# BPF.net
KiCad netlist of a schematic drawn in Altium Designer
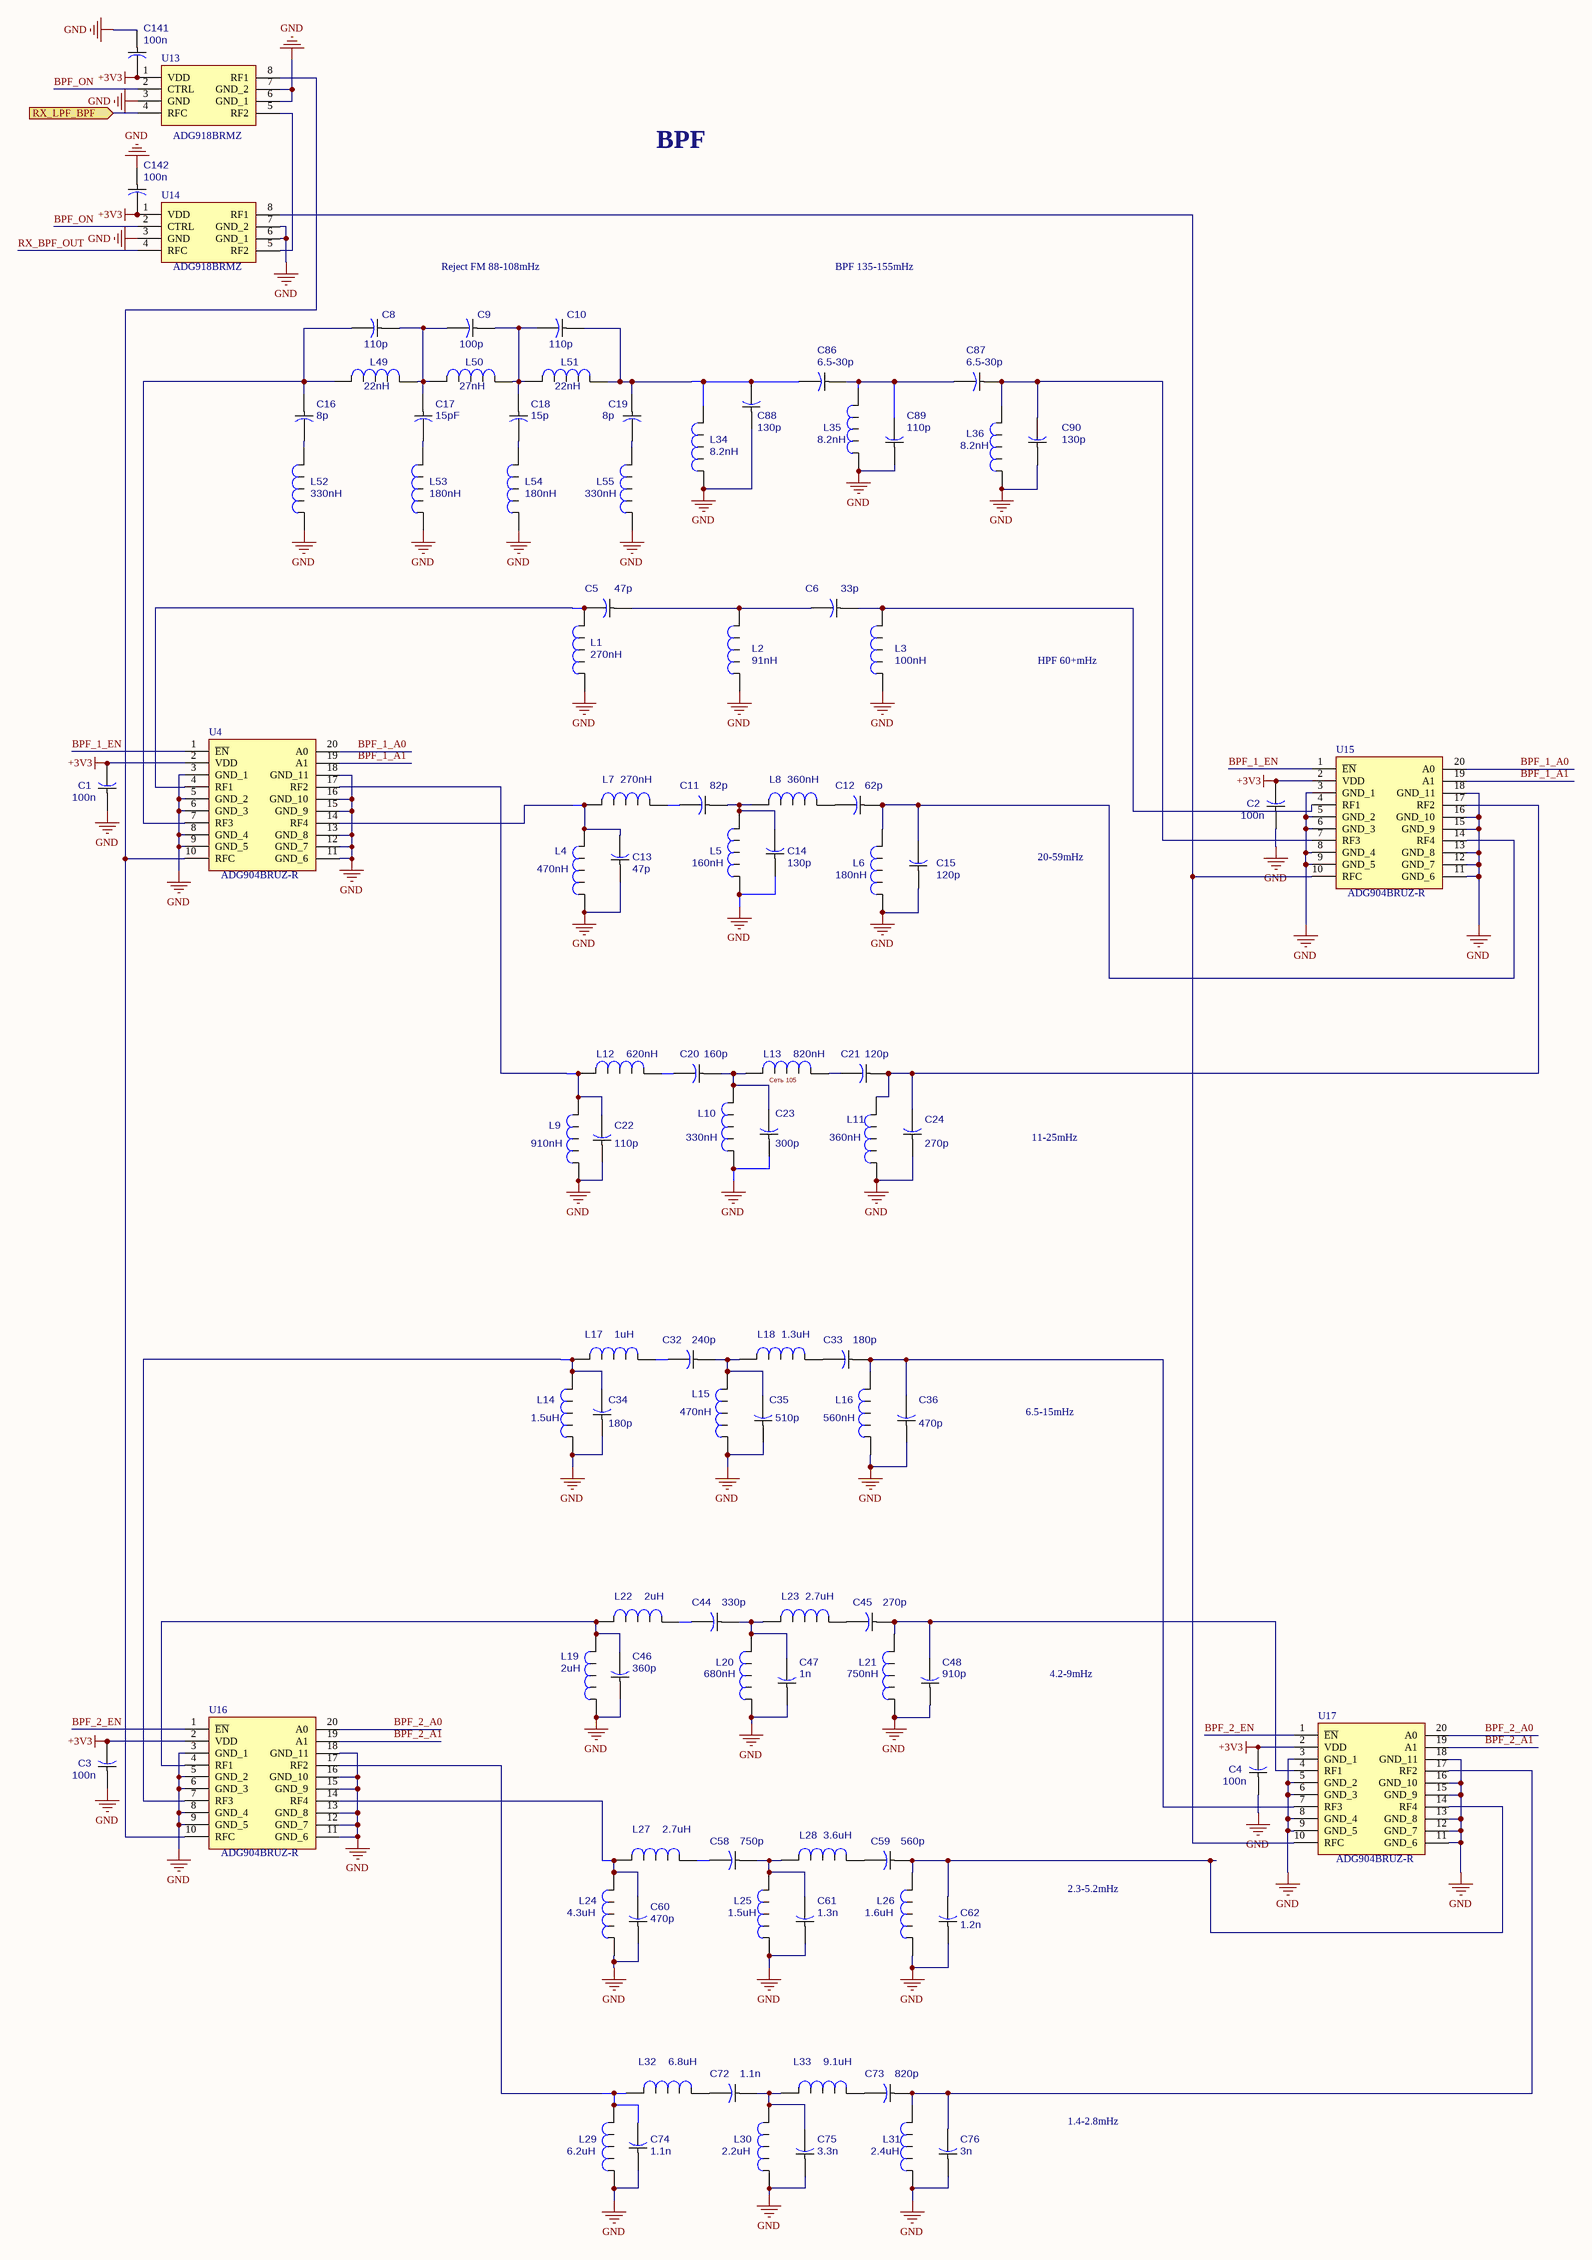
[diagram p0: BPF.SchDoc]

(export (version "E")
  (design (tool "Eeschema 10.0.6"))
  (components
    (comp (ref "C1")
      (value "100n")
      (footprint "CAP_0805")
      (description "CAP_0805")
      (libsource (lib "*") (part "CAP_0805"))
    )
    (comp (ref "C2")
      (value "100n")
      (footprint "CAP_0805")
      (description "CAP_0805")
      (libsource (lib "*") (part "CAP_0805"))
    )
    (comp (ref "C3")
      (value "100n")
      (footprint "CAP_0805")
      (description "CAP_0805")
      (libsource (lib "*") (part "CAP_0805"))
    )
    (comp (ref "C4")
      (value "100n")
      (footprint "CAP_0805")
      (description "CAP_0805")
      (libsource (lib "*") (part "CAP_0805"))
    )
    (comp (ref "C5")
      (value "47p")
      (footprint "CAP_0805")
      (description "CAP_0805")
      (libsource (lib "*") (part "CAP_0805"))
    )
    (comp (ref "C6")
      (value "33p")
      (footprint "CAP_0805")
      (description "CAP_0805")
      (libsource (lib "*") (part "CAP_0805"))
    )
    (comp (ref "C8")
      (value "110p")
      (footprint "CAP_0805")
      (description "CAP_0805")
      (libsource (lib "*") (part "CAP_0805"))
    )
    (comp (ref "C9")
      (value "100p")
      (footprint "CAP_0805")
      (description "CAP_0805")
      (libsource (lib "*") (part "CAP_0805"))
    )
    (comp (ref "C10")
      (value "110p")
      (footprint "CAP_0805")
      (description "CAP_0805")
      (libsource (lib "*") (part "CAP_0805"))
    )
    (comp (ref "C11")
      (value "82p")
      (footprint "CAP_0805")
      (description "CAP_0805")
      (libsource (lib "*") (part "CAP_0805"))
    )
    (comp (ref "C12")
      (value "62p")
      (footprint "CAP_0805")
      (description "CAP_0805")
      (libsource (lib "*") (part "CAP_0805"))
    )
    (comp (ref "C13")
      (value "47p")
      (footprint "CAP_0805")
      (description "CAP_0805")
      (libsource (lib "*") (part "CAP_0805"))
    )
    (comp (ref "C14")
      (value "130p")
      (footprint "CAP_0805")
      (description "CAP_0805")
      (libsource (lib "*") (part "CAP_0805"))
    )
    (comp (ref "C15")
      (value "120p")
      (footprint "CAP_0805")
      (description "CAP_0805")
      (libsource (lib "*") (part "CAP_0805"))
    )
    (comp (ref "C16")
      (value "8p")
      (footprint "CAP_0805")
      (description "CAP_0805")
      (libsource (lib "*") (part "CAP_0805"))
    )
    (comp (ref "C17")
      (value "15pF")
      (footprint "CAP_0805")
      (description "CAP_0805")
      (libsource (lib "*") (part "CAP_0805"))
    )
    (comp (ref "C18")
      (value "15p")
      (footprint "CAP_0805")
      (description "CAP_0805")
      (libsource (lib "*") (part "CAP_0805"))
    )
    (comp (ref "C19")
      (value "8p")
      (footprint "CAP_0805")
      (description "CAP_0805")
      (libsource (lib "*") (part "CAP_0805"))
    )
    (comp (ref "C20")
      (value "160p")
      (footprint "CAP_0805")
      (description "CAP_0805")
      (libsource (lib "*") (part "CAP_0805"))
    )
    (comp (ref "C21")
      (value "120p")
      (footprint "CAP_0805")
      (description "CAP_0805")
      (libsource (lib "*") (part "CAP_0805"))
    )
    (comp (ref "C22")
      (value "110p")
      (footprint "CAP_0805")
      (description "CAP_0805")
      (libsource (lib "*") (part "CAP_0805"))
    )
    (comp (ref "C23")
      (value "300p")
      (footprint "CAP_0805")
      (description "CAP_0805")
      (libsource (lib "*") (part "CAP_0805"))
    )
    (comp (ref "C24")
      (value "270p")
      (footprint "CAP_0805")
      (description "CAP_0805")
      (libsource (lib "*") (part "CAP_0805"))
    )
    (comp (ref "C32")
      (value "240p")
      (footprint "CAP_0805")
      (description "CAP_0805")
      (libsource (lib "*") (part "CAP_0805"))
    )
    (comp (ref "C33")
      (value "180p")
      (footprint "CAP_0805")
      (description "CAP_0805")
      (libsource (lib "*") (part "CAP_0805"))
    )
    (comp (ref "C34")
      (value "180p")
      (footprint "CAP_0805")
      (description "CAP_0805")
      (libsource (lib "*") (part "CAP_0805"))
    )
    (comp (ref "C35")
      (value "510p")
      (footprint "CAP_0805")
      (description "CAP_0805")
      (libsource (lib "*") (part "CAP_0805"))
    )
    (comp (ref "C36")
      (value "470p")
      (footprint "CAP_0805")
      (description "CAP_0805")
      (libsource (lib "*") (part "CAP_0805"))
    )
    (comp (ref "C44")
      (value "330p")
      (footprint "CAP_0805")
      (description "CAP_0805")
      (libsource (lib "*") (part "CAP_0805"))
    )
    (comp (ref "C45")
      (value "270p")
      (footprint "CAP_0805")
      (description "CAP_0805")
      (libsource (lib "*") (part "CAP_0805"))
    )
    (comp (ref "C46")
      (value "360p")
      (footprint "CAP_0805")
      (description "CAP_0805")
      (libsource (lib "*") (part "CAP_0805"))
    )
    (comp (ref "C47")
      (value "1n")
      (footprint "CAP_0805")
      (description "CAP_0805")
      (libsource (lib "*") (part "CAP_0805"))
    )
    (comp (ref "C48")
      (value "910p")
      (footprint "CAP_0805")
      (description "CAP_0805")
      (libsource (lib "*") (part "CAP_0805"))
    )
    (comp (ref "C58")
      (value "750p")
      (footprint "CAP_0805")
      (description "CAP_0805")
      (libsource (lib "*") (part "CAP_0805"))
    )
    (comp (ref "C59")
      (value "560p")
      (footprint "CAP_0805")
      (description "CAP_0805")
      (libsource (lib "*") (part "CAP_0805"))
    )
    (comp (ref "C60")
      (value "470p")
      (footprint "CAP_0805")
      (description "CAP_0805")
      (libsource (lib "*") (part "CAP_0805"))
    )
    (comp (ref "C61")
      (value "1.3n")
      (footprint "CAP_0805")
      (description "CAP_0805")
      (libsource (lib "*") (part "CAP_0805"))
    )
    (comp (ref "C62")
      (value "1.2n")
      (footprint "CAP_0805")
      (description "CAP_0805")
      (libsource (lib "*") (part "CAP_0805"))
    )
    (comp (ref "C72")
      (value "1.1n")
      (footprint "CAP_0805")
      (description "CAP_0805")
      (libsource (lib "*") (part "CAP_0805"))
    )
    (comp (ref "C73")
      (value "820p")
      (footprint "CAP_0805")
      (description "CAP_0805")
      (libsource (lib "*") (part "CAP_0805"))
    )
    (comp (ref "C74")
      (value "1.1n")
      (footprint "CAP_0805")
      (description "CAP_0805")
      (libsource (lib "*") (part "CAP_0805"))
    )
    (comp (ref "C75")
      (value "3.3n")
      (footprint "CAP_0805")
      (description "CAP_0805")
      (libsource (lib "*") (part "CAP_0805"))
    )
    (comp (ref "C76")
      (value "3n")
      (footprint "CAP_0805")
      (description "CAP_0805")
      (libsource (lib "*") (part "CAP_0805"))
    )
    (comp (ref "C86")
      (value "6.5-30p")
      (footprint "5025[2010]")
      (description "TZC3P300A110")
      (libsource (lib "*") (part "CAP_0805"))
    )
    (comp (ref "C87")
      (value "6.5-30p")
      (footprint "5025[2010]")
      (description "TZC3P300A110")
      (libsource (lib "*") (part "CAP_0805"))
    )
    (comp (ref "C88")
      (value "130p")
      (footprint "CAP_0805")
      (description "CAP_0805")
      (libsource (lib "*") (part "CAP_0805"))
    )
    (comp (ref "C89")
      (value "110p")
      (footprint "CAP_0805")
      (description "CAP_0805")
      (libsource (lib "*") (part "CAP_0805"))
    )
    (comp (ref "C90")
      (value "130p")
      (footprint "CAP_0805")
      (description "CAP_0805")
      (libsource (lib "*") (part "CAP_0805"))
    )
    (comp (ref "C141")
      (value "100n")
      (footprint "CAP_0805")
      (description "CAP_0805")
      (libsource (lib "*") (part "CAP_0805"))
    )
    (comp (ref "C142")
      (value "100n")
      (footprint "CAP_0805")
      (description "CAP_0805")
      (libsource (lib "*") (part "CAP_0805"))
    )
    (comp (ref "L1")
      (value "270nH")
      (footprint "IND_0805")
      (description "IND_0805")
      (libsource (lib "*") (part "IND_0805"))
    )
    (comp (ref "L2")
      (value "91nH")
      (footprint "IND_0805")
      (description "IND_0805")
      (libsource (lib "*") (part "IND_0805"))
    )
    (comp (ref "L3")
      (value "100nH")
      (footprint "IND_0805")
      (description "IND_0805")
      (libsource (lib "*") (part "IND_0805"))
    )
    (comp (ref "L4")
      (value "470nH")
      (footprint "IND_0805")
      (description "IND_0805")
      (libsource (lib "*") (part "IND_0805"))
    )
    (comp (ref "L5")
      (value "160nH")
      (footprint "IND_0805")
      (description "IND_0805")
      (libsource (lib "*") (part "IND_0805"))
    )
    (comp (ref "L6")
      (value "180nH")
      (footprint "IND_0805")
      (description "IND_0805")
      (libsource (lib "*") (part "IND_0805"))
    )
    (comp (ref "L7")
      (value "270nH")
      (footprint "IND_0805")
      (description "IND_0805")
      (libsource (lib "*") (part "IND_0805"))
    )
    (comp (ref "L8")
      (value "360nH")
      (footprint "IND_0805")
      (description "IND_0805")
      (libsource (lib "*") (part "IND_0805"))
    )
    (comp (ref "L9")
      (value "910nH")
      (footprint "IND_0805")
      (description "IND_0805")
      (libsource (lib "*") (part "IND_0805"))
    )
    (comp (ref "L10")
      (value "330nH")
      (footprint "IND_0805")
      (description "IND_0805")
      (libsource (lib "*") (part "IND_0805"))
    )
    (comp (ref "L11")
      (value "360nH")
      (footprint "IND_0805")
      (description "IND_0805")
      (libsource (lib "*") (part "IND_0805"))
    )
    (comp (ref "L12")
      (value "620nH")
      (footprint "IND_0805")
      (description "IND_0805")
      (libsource (lib "*") (part "IND_0805"))
    )
    (comp (ref "L13")
      (value "820nH")
      (footprint "IND_0805")
      (description "IND_0805")
      (libsource (lib "*") (part "IND_0805"))
    )
    (comp (ref "L14")
      (value "1.5uH")
      (footprint "IND_0805")
      (description "IND_0805")
      (libsource (lib "*") (part "IND_0805"))
    )
    (comp (ref "L15")
      (value "470nH")
      (footprint "IND_0805")
      (description "IND_0805")
      (libsource (lib "*") (part "IND_0805"))
    )
    (comp (ref "L16")
      (value "560nH")
      (footprint "IND_0805")
      (description "IND_0805")
      (libsource (lib "*") (part "IND_0805"))
    )
    (comp (ref "L17")
      (value "1uH")
      (footprint "IND_0805")
      (description "IND_0805")
      (libsource (lib "*") (part "IND_0805"))
    )
    (comp (ref "L18")
      (value "1.3uH")
      (footprint "IND_0805")
      (description "IND_0805")
      (libsource (lib "*") (part "IND_0805"))
    )
    (comp (ref "L19")
      (value "2uH")
      (footprint "IND_0805")
      (description "IND_0805")
      (libsource (lib "*") (part "IND_0805"))
    )
    (comp (ref "L20")
      (value "680nH")
      (footprint "IND_0805")
      (description "IND_0805")
      (libsource (lib "*") (part "IND_0805"))
    )
    (comp (ref "L21")
      (value "750nH")
      (footprint "IND_0805")
      (description "IND_0805")
      (libsource (lib "*") (part "IND_0805"))
    )
    (comp (ref "L22")
      (value "2uH")
      (footprint "IND_0805")
      (description "IND_0805")
      (libsource (lib "*") (part "IND_0805"))
    )
    (comp (ref "L23")
      (value "2.7uH")
      (footprint "IND_0805")
      (description "IND_0805")
      (libsource (lib "*") (part "IND_0805"))
    )
    (comp (ref "L24")
      (value "4.3uH")
      (footprint "IND_0805")
      (description "IND_0805")
      (libsource (lib "*") (part "IND_0805"))
    )
    (comp (ref "L25")
      (value "1.5uH")
      (footprint "IND_0805")
      (description "IND_0805")
      (libsource (lib "*") (part "IND_0805"))
    )
    (comp (ref "L26")
      (value "1.6uH")
      (footprint "IND_0805")
      (description "IND_0805")
      (libsource (lib "*") (part "IND_0805"))
    )
    (comp (ref "L27")
      (value "2.7uH")
      (footprint "IND_0805")
      (description "IND_0805")
      (libsource (lib "*") (part "IND_0805"))
    )
    (comp (ref "L28")
      (value "3.6uH")
      (footprint "IND_0805")
      (description "IND_0805")
      (libsource (lib "*") (part "IND_0805"))
    )
    (comp (ref "L29")
      (value "6.2uH")
      (footprint "IND_0805")
      (description "IND_0805")
      (libsource (lib "*") (part "IND_0805"))
    )
    (comp (ref "L30")
      (value "2.2uH")
      (footprint "IND_0805")
      (description "IND_0805")
      (libsource (lib "*") (part "IND_0805"))
    )
    (comp (ref "L31")
      (value "2.4uH")
      (footprint "IND_0805")
      (description "IND_0805")
      (libsource (lib "*") (part "IND_0805"))
    )
    (comp (ref "L32")
      (value "6.8uH")
      (footprint "IND_0805")
      (description "IND_0805")
      (libsource (lib "*") (part "IND_0805"))
    )
    (comp (ref "L33")
      (value "9.1uH")
      (footprint "IND_0805")
      (description "IND_0805")
      (libsource (lib "*") (part "IND_0805"))
    )
    (comp (ref "L34")
      (value "8.2nH")
      (footprint "IND_0805")
      (description "IND_0805")
      (libsource (lib "*") (part "IND_0805"))
    )
    (comp (ref "L35")
      (value "8.2nH")
      (footprint "IND_0805")
      (description "IND_0805")
      (libsource (lib "*") (part "IND_0805"))
    )
    (comp (ref "L36")
      (value "8.2nH")
      (footprint "IND_0805")
      (description "IND_0805")
      (libsource (lib "*") (part "IND_0805"))
    )
    (comp (ref "L49")
      (value "22nH")
      (footprint "IND_0805")
      (description "IND_0805")
      (libsource (lib "*") (part "IND_0805"))
    )
    (comp (ref "L50")
      (value "27nH")
      (footprint "IND_0805")
      (description "IND_0805")
      (libsource (lib "*") (part "IND_0805"))
    )
    (comp (ref "L51")
      (value "22nH")
      (footprint "IND_0805")
      (description "IND_0805")
      (libsource (lib "*") (part "IND_0805"))
    )
    (comp (ref "L52")
      (value "330nH")
      (footprint "IND_0805")
      (description "IND_0805")
      (libsource (lib "*") (part "IND_0805"))
    )
    (comp (ref "L53")
      (value "180nH")
      (footprint "IND_0805")
      (description "IND_0805")
      (libsource (lib "*") (part "IND_0805"))
    )
    (comp (ref "L54")
      (value "180nH")
      (footprint "IND_0805")
      (description "IND_0805")
      (libsource (lib "*") (part "IND_0805"))
    )
    (comp (ref "L55")
      (value "330nH")
      (footprint "IND_0805")
      (description "IND_0805")
      (libsource (lib "*") (part "IND_0805"))
    )
    (comp (ref "U4")
      (value "ADG904BRUZ-R")
      (footprint "SamacSys:SOP65P640X120-20N")
      (description "Integrated Circuit")
      (fields
        (field (name "MOUSER PART NUMBER") "584-ADG904BRUZ-R")
        (field (name "RS PART NUMBER") "5385019P")
      )
      (libsource (lib "*") (part "ADG904BRUZ-R"))
    )
    (comp (ref "U13")
      (value "ADG918BRMZ")
      (footprint "SamacSys:SOP65P490X110-8N")
      (description "Integrated Circuit")
      (fields (field (name "MOUSER PART NUMBER") "584-ADG918BRMZ") (field (name "RS PART NUMBER") "4969212P"))
      (libsource (lib "*") (part "ADG918BRMZ"))
    )
    (comp (ref "U14")
      (value "ADG918BRMZ")
      (footprint "SamacSys:SOP65P490X110-8N")
      (description "Integrated Circuit")
      (fields (field (name "MOUSER PART NUMBER") "584-ADG918BRMZ") (field (name "RS PART NUMBER") "4969212P"))
      (libsource (lib "*") (part "ADG918BRMZ"))
    )
    (comp (ref "U15")
      (value "ADG904BRUZ-R")
      (footprint "SamacSys:SOP65P640X120-20N")
      (description "Integrated Circuit")
      (fields
        (field (name "MOUSER PART NUMBER") "584-ADG904BRUZ-R")
        (field (name "RS PART NUMBER") "5385019P")
      )
      (libsource (lib "*") (part "ADG904BRUZ-R"))
    )
    (comp (ref "U16")
      (value "ADG904BRUZ-R")
      (footprint "SamacSys:SOP65P640X120-20N")
      (description "Integrated Circuit")
      (fields
        (field (name "MOUSER PART NUMBER") "584-ADG904BRUZ-R")
        (field (name "RS PART NUMBER") "5385019P")
      )
      (libsource (lib "*") (part "ADG904BRUZ-R"))
    )
    (comp (ref "U17")
      (value "ADG904BRUZ-R")
      (footprint "SamacSys:SOP65P640X120-20N")
      (description "Integrated Circuit")
      (fields
        (field (name "MOUSER PART NUMBER") "584-ADG904BRUZ-R")
        (field (name "RS PART NUMBER") "5385019P")
      )
      (libsource (lib "*") (part "ADG904BRUZ-R"))
    )
  )
  (nets
    (net (code "1") (name "+3V3") (class "Default")
      (node (ref "C1") (pin "2") (pinfunction "2_2") (pintype "passive"))
      (node (ref "C141") (pin "2") (pinfunction "2_2") (pintype "passive"))
      (node (ref "C142") (pin "2") (pinfunction "2_2") (pintype "passive"))
      (node (ref "C2") (pin "2") (pinfunction "2_2") (pintype "passive"))
      (node (ref "C3") (pin "2") (pinfunction "2_2") (pintype "passive"))
      (node (ref "C4") (pin "2") (pinfunction "2_2") (pintype "passive"))
      (node (ref "U13") (pin "1") (pinfunction "VDD_1") (pintype "power_in"))
      (node (ref "U14") (pin "1") (pinfunction "VDD_1") (pintype "power_in"))
      (node (ref "U15") (pin "2") (pinfunction "VDD_2") (pintype "passive"))
      (node (ref "U16") (pin "2") (pinfunction "VDD_2") (pintype "passive"))
      (node (ref "U17") (pin "2") (pinfunction "VDD_2") (pintype "passive"))
      (node (ref "U4") (pin "2") (pinfunction "VDD_2") (pintype "passive"))
    )
    (net (code "2") (name "/BPF_1_A0") (class "Default")
      (node (ref "U15") (pin "20") (pinfunction "A0_20") (pintype "passive"))
      (node (ref "U4") (pin "20") (pinfunction "A0_20") (pintype "passive"))
    )
    (net (code "3") (name "/BPF_1_A1") (class "Default")
      (node (ref "U15") (pin "19") (pinfunction "A1_19") (pintype "passive"))
      (node (ref "U4") (pin "19") (pinfunction "A1_19") (pintype "passive"))
    )
    (net (code "4") (name "/BPF_1_EN") (class "Default")
      (node (ref "U15") (pin "1") (pinfunction "~{EN}_1") (pintype "passive"))
      (node (ref "U4") (pin "1") (pinfunction "~{EN}_1") (pintype "passive"))
    )
    (net (code "5") (name "/BPF_2_A0") (class "Default")
      (node (ref "U16") (pin "20") (pinfunction "A0_20") (pintype "passive"))
      (node (ref "U17") (pin "20") (pinfunction "A0_20") (pintype "passive"))
    )
    (net (code "6") (name "/BPF_2_A1") (class "Default")
      (node (ref "U16") (pin "19") (pinfunction "A1_19") (pintype "passive"))
      (node (ref "U17") (pin "19") (pinfunction "A1_19") (pintype "passive"))
    )
    (net (code "7") (name "/BPF_2_EN") (class "Default")
      (node (ref "U16") (pin "1") (pinfunction "~{EN}_1") (pintype "passive"))
      (node (ref "U17") (pin "1") (pinfunction "~{EN}_1") (pintype "passive"))
    )
    (net (code "8") (name "/BPF_ON") (class "Default")
      (node (ref "U13") (pin "2") (pinfunction "CTRL_2") (pintype "passive"))
      (node (ref "U14") (pin "2") (pinfunction "CTRL_2") (pintype "passive"))
    )
    (net (code "9") (name "/RX_BPF_OUT") (class "Default")
      (node (ref "U14") (pin "4") (pinfunction "RFC_4") (pintype "passive"))
    )
    (net (code "10") (name "/RX_LPF_BPF") (class "Default")
      (node (ref "U13") (pin "4") (pinfunction "RFC_4") (pintype "passive"))
    )
    (net (code "11") (name "/Сеть 105") (class "Default")
      (node (ref "C20") (pin "1") (pinfunction "1_1") (pintype "passive"))
      (node (ref "C23") (pin "2") (pinfunction "2_2") (pintype "passive"))
      (node (ref "L10") (pin "2") (pinfunction "2_2") (pintype "passive"))
      (node (ref "L13") (pin "1") (pinfunction "1_1") (pintype "passive"))
    )
    (net (code "12") (name "GND") (class "Default")
      (node (ref "C1") (pin "1") (pinfunction "1_1") (pintype "passive"))
      (node (ref "C13") (pin "1") (pinfunction "1_1") (pintype "passive"))
      (node (ref "C14") (pin "1") (pinfunction "1_1") (pintype "passive"))
      (node (ref "C141") (pin "1") (pinfunction "1_1") (pintype "passive"))
      (node (ref "C142") (pin "1") (pinfunction "1_1") (pintype "passive"))
      (node (ref "C15") (pin "1") (pinfunction "1_1") (pintype "passive"))
      (node (ref "C2") (pin "1") (pinfunction "1_1") (pintype "passive"))
      (node (ref "C22") (pin "1") (pinfunction "1_1") (pintype "passive"))
      (node (ref "C23") (pin "1") (pinfunction "1_1") (pintype "passive"))
      (node (ref "C24") (pin "1") (pinfunction "1_1") (pintype "passive"))
      (node (ref "C3") (pin "1") (pinfunction "1_1") (pintype "passive"))
      (node (ref "C34") (pin "1") (pinfunction "1_1") (pintype "passive"))
      (node (ref "C35") (pin "1") (pinfunction "1_1") (pintype "passive"))
      (node (ref "C36") (pin "1") (pinfunction "1_1") (pintype "passive"))
      (node (ref "C4") (pin "1") (pinfunction "1_1") (pintype "passive"))
      (node (ref "C46") (pin "1") (pinfunction "1_1") (pintype "passive"))
      (node (ref "C47") (pin "1") (pinfunction "1_1") (pintype "passive"))
      (node (ref "C48") (pin "1") (pinfunction "1_1") (pintype "passive"))
      (node (ref "C60") (pin "1") (pinfunction "1_1") (pintype "passive"))
      (node (ref "C61") (pin "1") (pinfunction "1_1") (pintype "passive"))
      (node (ref "C62") (pin "1") (pinfunction "1_1") (pintype "passive"))
      (node (ref "C74") (pin "1") (pinfunction "1_1") (pintype "passive"))
      (node (ref "C75") (pin "1") (pinfunction "1_1") (pintype "passive"))
      (node (ref "C76") (pin "1") (pinfunction "1_1") (pintype "passive"))
      (node (ref "C88") (pin "1") (pinfunction "1_1") (pintype "passive"))
      (node (ref "C89") (pin "1") (pinfunction "1_1") (pintype "passive"))
      (node (ref "C90") (pin "1") (pinfunction "1_1") (pintype "passive"))
      (node (ref "L1") (pin "1") (pinfunction "1_1") (pintype "passive"))
      (node (ref "L10") (pin "1") (pinfunction "1_1") (pintype "passive"))
      (node (ref "L11") (pin "1") (pinfunction "1_1") (pintype "passive"))
      (node (ref "L14") (pin "1") (pinfunction "1_1") (pintype "passive"))
      (node (ref "L15") (pin "1") (pinfunction "1_1") (pintype "passive"))
      (node (ref "L16") (pin "1") (pinfunction "1_1") (pintype "passive"))
      (node (ref "L19") (pin "1") (pinfunction "1_1") (pintype "passive"))
      (node (ref "L2") (pin "1") (pinfunction "1_1") (pintype "passive"))
      (node (ref "L20") (pin "1") (pinfunction "1_1") (pintype "passive"))
      (node (ref "L21") (pin "1") (pinfunction "1_1") (pintype "passive"))
      (node (ref "L24") (pin "1") (pinfunction "1_1") (pintype "passive"))
      (node (ref "L25") (pin "1") (pinfunction "1_1") (pintype "passive"))
      (node (ref "L26") (pin "1") (pinfunction "1_1") (pintype "passive"))
      (node (ref "L29") (pin "1") (pinfunction "1_1") (pintype "passive"))
      (node (ref "L3") (pin "1") (pinfunction "1_1") (pintype "passive"))
      (node (ref "L30") (pin "1") (pinfunction "1_1") (pintype "passive"))
      (node (ref "L31") (pin "1") (pinfunction "1_1") (pintype "passive"))
      (node (ref "L34") (pin "1") (pinfunction "1_1") (pintype "passive"))
      (node (ref "L35") (pin "1") (pinfunction "1_1") (pintype "passive"))
      (node (ref "L36") (pin "1") (pinfunction "1_1") (pintype "passive"))
      (node (ref "L4") (pin "1") (pinfunction "1_1") (pintype "passive"))
      (node (ref "L5") (pin "1") (pinfunction "1_1") (pintype "passive"))
      (node (ref "L52") (pin "1") (pinfunction "1_1") (pintype "passive"))
      (node (ref "L53") (pin "1") (pinfunction "1_1") (pintype "passive"))
      (node (ref "L54") (pin "1") (pinfunction "1_1") (pintype "passive"))
      (node (ref "L55") (pin "1") (pinfunction "1_1") (pintype "passive"))
      (node (ref "L6") (pin "1") (pinfunction "1_1") (pintype "passive"))
      (node (ref "L9") (pin "1") (pinfunction "1_1") (pintype "passive"))
      (node (ref "U13") (pin "3") (pinfunction "GND_3") (pintype "power_in"))
      (node (ref "U13") (pin "6") (pinfunction "GND_1_6") (pintype "power_in"))
      (node (ref "U13") (pin "7") (pinfunction "GND_2_7") (pintype "power_in"))
      (node (ref "U14") (pin "3") (pinfunction "GND_3") (pintype "power_in"))
      (node (ref "U14") (pin "6") (pinfunction "GND_1_6") (pintype "power_in"))
      (node (ref "U14") (pin "7") (pinfunction "GND_2_7") (pintype "power_in"))
      (node (ref "U15") (pin "11") (pinfunction "GND_6_11") (pintype "passive"))
      (node (ref "U15") (pin "12") (pinfunction "GND_7_12") (pintype "passive"))
      (node (ref "U15") (pin "13") (pinfunction "GND_8_13") (pintype "passive"))
      (node (ref "U15") (pin "15") (pinfunction "GND_9_15") (pintype "passive"))
      (node (ref "U15") (pin "16") (pinfunction "GND_10_16") (pintype "passive"))
      (node (ref "U15") (pin "18") (pinfunction "GND_11_18") (pintype "passive"))
      (node (ref "U15") (pin "3") (pinfunction "GND_1_3") (pintype "passive"))
      (node (ref "U15") (pin "5") (pinfunction "GND_2_5") (pintype "passive"))
      (node (ref "U15") (pin "6") (pinfunction "GND_3_6") (pintype "passive"))
      (node (ref "U15") (pin "8") (pinfunction "GND_4_8") (pintype "passive"))
      (node (ref "U15") (pin "9") (pinfunction "GND_5_9") (pintype "passive"))
      (node (ref "U16") (pin "11") (pinfunction "GND_6_11") (pintype "passive"))
      (node (ref "U16") (pin "12") (pinfunction "GND_7_12") (pintype "passive"))
      (node (ref "U16") (pin "13") (pinfunction "GND_8_13") (pintype "passive"))
      (node (ref "U16") (pin "15") (pinfunction "GND_9_15") (pintype "passive"))
      (node (ref "U16") (pin "16") (pinfunction "GND_10_16") (pintype "passive"))
      (node (ref "U16") (pin "18") (pinfunction "GND_11_18") (pintype "passive"))
      (node (ref "U16") (pin "3") (pinfunction "GND_1_3") (pintype "passive"))
      (node (ref "U16") (pin "5") (pinfunction "GND_2_5") (pintype "passive"))
      (node (ref "U16") (pin "6") (pinfunction "GND_3_6") (pintype "passive"))
      (node (ref "U16") (pin "8") (pinfunction "GND_4_8") (pintype "passive"))
      (node (ref "U16") (pin "9") (pinfunction "GND_5_9") (pintype "passive"))
      (node (ref "U17") (pin "11") (pinfunction "GND_6_11") (pintype "passive"))
      (node (ref "U17") (pin "12") (pinfunction "GND_7_12") (pintype "passive"))
      (node (ref "U17") (pin "13") (pinfunction "GND_8_13") (pintype "passive"))
      (node (ref "U17") (pin "15") (pinfunction "GND_9_15") (pintype "passive"))
      (node (ref "U17") (pin "16") (pinfunction "GND_10_16") (pintype "passive"))
      (node (ref "U17") (pin "18") (pinfunction "GND_11_18") (pintype "passive"))
      (node (ref "U17") (pin "3") (pinfunction "GND_1_3") (pintype "passive"))
      (node (ref "U17") (pin "5") (pinfunction "GND_2_5") (pintype "passive"))
      (node (ref "U17") (pin "6") (pinfunction "GND_3_6") (pintype "passive"))
      (node (ref "U17") (pin "8") (pinfunction "GND_4_8") (pintype "passive"))
      (node (ref "U17") (pin "9") (pinfunction "GND_5_9") (pintype "passive"))
      (node (ref "U4") (pin "11") (pinfunction "GND_6_11") (pintype "passive"))
      (node (ref "U4") (pin "12") (pinfunction "GND_7_12") (pintype "passive"))
      (node (ref "U4") (pin "13") (pinfunction "GND_8_13") (pintype "passive"))
      (node (ref "U4") (pin "15") (pinfunction "GND_9_15") (pintype "passive"))
      (node (ref "U4") (pin "16") (pinfunction "GND_10_16") (pintype "passive"))
      (node (ref "U4") (pin "18") (pinfunction "GND_11_18") (pintype "passive"))
      (node (ref "U4") (pin "3") (pinfunction "GND_1_3") (pintype "passive"))
      (node (ref "U4") (pin "5") (pinfunction "GND_2_5") (pintype "passive"))
      (node (ref "U4") (pin "6") (pinfunction "GND_3_6") (pintype "passive"))
      (node (ref "U4") (pin "8") (pinfunction "GND_4_8") (pintype "passive"))
      (node (ref "U4") (pin "9") (pinfunction "GND_5_9") (pintype "passive"))
    )
    (net (code "13") (name "Net-(C5-Pad1)") (class "Default")
      (node (ref "C5") (pin "1") (pinfunction "1_1") (pintype "passive"))
      (node (ref "C6") (pin "2") (pinfunction "2_2") (pintype "passive"))
      (node (ref "L2") (pin "2") (pinfunction "2_2") (pintype "passive"))
    )
    (net (code "14") (name "Net-(C10-Pad1)") (class "Default")
      (node (ref "C10") (pin "1") (pinfunction "1_1") (pintype "passive"))
      (node (ref "C19") (pin "1") (pinfunction "1_1") (pintype "passive"))
      (node (ref "C86") (pin "2") (pinfunction "2_2") (pintype "passive"))
      (node (ref "C88") (pin "2") (pinfunction "2_2") (pintype "passive"))
      (node (ref "L34") (pin "2") (pinfunction "2_2") (pintype "passive"))
      (node (ref "L51") (pin "2") (pinfunction "2_2") (pintype "passive"))
    )
    (net (code "15") (name "Net-(C10-Pad2)") (class "Default")
      (node (ref "C10") (pin "2") (pinfunction "2_2") (pintype "passive"))
      (node (ref "C18") (pin "1") (pinfunction "1_1") (pintype "passive"))
      (node (ref "C9") (pin "1") (pinfunction "1_1") (pintype "passive"))
      (node (ref "L50") (pin "2") (pinfunction "2_2") (pintype "passive"))
      (node (ref "L51") (pin "1") (pinfunction "1_1") (pintype "passive"))
    )
    (net (code "16") (name "Net-(C11-Pad1)") (class "Default")
      (node (ref "C11") (pin "1") (pinfunction "1_1") (pintype "passive"))
      (node (ref "C14") (pin "2") (pinfunction "2_2") (pintype "passive"))
      (node (ref "L5") (pin "2") (pinfunction "2_2") (pintype "passive"))
      (node (ref "L8") (pin "1") (pinfunction "1_1") (pintype "passive"))
    )
    (net (code "17") (name "Net-(C11-Pad2)") (class "Default")
      (node (ref "C11") (pin "2") (pinfunction "2_2") (pintype "passive"))
      (node (ref "L7") (pin "2") (pinfunction "2_2") (pintype "passive"))
    )
    (net (code "18") (name "Net-(C12-Pad2)") (class "Default")
      (node (ref "C12") (pin "2") (pinfunction "2_2") (pintype "passive"))
      (node (ref "L8") (pin "2") (pinfunction "2_2") (pintype "passive"))
    )
    (net (code "19") (name "Net-(C16-Pad2)") (class "Default")
      (node (ref "C16") (pin "2") (pinfunction "2_2") (pintype "passive"))
      (node (ref "L52") (pin "2") (pinfunction "2_2") (pintype "passive"))
    )
    (net (code "20") (name "Net-(C17-Pad1)") (class "Default")
      (node (ref "C17") (pin "1") (pinfunction "1_1") (pintype "passive"))
      (node (ref "C8") (pin "1") (pinfunction "1_1") (pintype "passive"))
      (node (ref "C9") (pin "2") (pinfunction "2_2") (pintype "passive"))
      (node (ref "L49") (pin "2") (pinfunction "2_2") (pintype "passive"))
      (node (ref "L50") (pin "1") (pinfunction "1_1") (pintype "passive"))
    )
    (net (code "21") (name "Net-(C17-Pad2)") (class "Default")
      (node (ref "C17") (pin "2") (pinfunction "2_2") (pintype "passive"))
      (node (ref "L53") (pin "2") (pinfunction "2_2") (pintype "passive"))
    )
    (net (code "22") (name "Net-(C18-Pad2)") (class "Default")
      (node (ref "C18") (pin "2") (pinfunction "2_2") (pintype "passive"))
      (node (ref "L54") (pin "2") (pinfunction "2_2") (pintype "passive"))
    )
    (net (code "23") (name "Net-(C19-Pad2)") (class "Default")
      (node (ref "C19") (pin "2") (pinfunction "2_2") (pintype "passive"))
      (node (ref "L55") (pin "2") (pinfunction "2_2") (pintype "passive"))
    )
    (net (code "24") (name "Net-(C20-Pad2)") (class "Default")
      (node (ref "C20") (pin "2") (pinfunction "2_2") (pintype "passive"))
      (node (ref "L12") (pin "2") (pinfunction "2_2") (pintype "passive"))
    )
    (net (code "25") (name "Net-(C21-Pad2)") (class "Default")
      (node (ref "C21") (pin "2") (pinfunction "2_2") (pintype "passive"))
      (node (ref "L13") (pin "2") (pinfunction "2_2") (pintype "passive"))
    )
    (net (code "26") (name "Net-(C32-Pad1)") (class "Default")
      (node (ref "C32") (pin "1") (pinfunction "1_1") (pintype "passive"))
      (node (ref "C35") (pin "2") (pinfunction "2_2") (pintype "passive"))
      (node (ref "L15") (pin "2") (pinfunction "2_2") (pintype "passive"))
      (node (ref "L18") (pin "1") (pinfunction "1_1") (pintype "passive"))
    )
    (net (code "27") (name "Net-(C32-Pad2)") (class "Default")
      (node (ref "C32") (pin "2") (pinfunction "2_2") (pintype "passive"))
      (node (ref "L17") (pin "2") (pinfunction "2_2") (pintype "passive"))
    )
    (net (code "28") (name "Net-(C33-Pad2)") (class "Default")
      (node (ref "C33") (pin "2") (pinfunction "2_2") (pintype "passive"))
      (node (ref "L18") (pin "2") (pinfunction "2_2") (pintype "passive"))
    )
    (net (code "29") (name "Net-(C44-Pad1)") (class "Default")
      (node (ref "C44") (pin "1") (pinfunction "1_1") (pintype "passive"))
      (node (ref "C47") (pin "2") (pinfunction "2_2") (pintype "passive"))
      (node (ref "L20") (pin "2") (pinfunction "2_2") (pintype "passive"))
      (node (ref "L23") (pin "1") (pinfunction "1_1") (pintype "passive"))
    )
    (net (code "30") (name "Net-(C44-Pad2)") (class "Default")
      (node (ref "C44") (pin "2") (pinfunction "2_2") (pintype "passive"))
      (node (ref "L22") (pin "2") (pinfunction "2_2") (pintype "passive"))
    )
    (net (code "31") (name "Net-(C45-Pad2)") (class "Default")
      (node (ref "C45") (pin "2") (pinfunction "2_2") (pintype "passive"))
      (node (ref "L23") (pin "2") (pinfunction "2_2") (pintype "passive"))
    )
    (net (code "32") (name "Net-(C58-Pad1)") (class "Default")
      (node (ref "C58") (pin "1") (pinfunction "1_1") (pintype "passive"))
      (node (ref "C61") (pin "2") (pinfunction "2_2") (pintype "passive"))
      (node (ref "L25") (pin "2") (pinfunction "2_2") (pintype "passive"))
      (node (ref "L28") (pin "1") (pinfunction "1_1") (pintype "passive"))
    )
    (net (code "33") (name "Net-(C58-Pad2)") (class "Default")
      (node (ref "C58") (pin "2") (pinfunction "2_2") (pintype "passive"))
      (node (ref "L27") (pin "2") (pinfunction "2_2") (pintype "passive"))
    )
    (net (code "34") (name "Net-(C59-Pad2)") (class "Default")
      (node (ref "C59") (pin "2") (pinfunction "2_2") (pintype "passive"))
      (node (ref "L28") (pin "2") (pinfunction "2_2") (pintype "passive"))
    )
    (net (code "35") (name "Net-(C72-Pad1)") (class "Default")
      (node (ref "C72") (pin "1") (pinfunction "1_1") (pintype "passive"))
      (node (ref "C75") (pin "2") (pinfunction "2_2") (pintype "passive"))
      (node (ref "L30") (pin "2") (pinfunction "2_2") (pintype "passive"))
      (node (ref "L33") (pin "1") (pinfunction "1_1") (pintype "passive"))
    )
    (net (code "36") (name "Net-(C72-Pad2)") (class "Default")
      (node (ref "C72") (pin "2") (pinfunction "2_2") (pintype "passive"))
      (node (ref "L32") (pin "2") (pinfunction "2_2") (pintype "passive"))
    )
    (net (code "37") (name "Net-(C73-Pad2)") (class "Default")
      (node (ref "C73") (pin "2") (pinfunction "2_2") (pintype "passive"))
      (node (ref "L33") (pin "2") (pinfunction "2_2") (pintype "passive"))
    )
    (net (code "38") (name "Net-(C86-Pad1)") (class "Default")
      (node (ref "C86") (pin "1") (pinfunction "1_1") (pintype "passive"))
      (node (ref "C87") (pin "2") (pinfunction "2_2") (pintype "passive"))
      (node (ref "C89") (pin "2") (pinfunction "2_2") (pintype "passive"))
      (node (ref "L35") (pin "2") (pinfunction "2_2") (pintype "passive"))
    )
    (net (code "39") (name "Net-(U4-RF1)") (class "Default")
      (node (ref "C5") (pin "2") (pinfunction "2_2") (pintype "passive"))
      (node (ref "L1") (pin "2") (pinfunction "2_2") (pintype "passive"))
      (node (ref "U4") (pin "4") (pinfunction "RF1_4") (pintype "passive"))
    )
    (net (code "40") (name "Net-(U4-RF2)") (class "Default")
      (node (ref "C22") (pin "2") (pinfunction "2_2") (pintype "passive"))
      (node (ref "L12") (pin "1") (pinfunction "1_1") (pintype "passive"))
      (node (ref "L9") (pin "2") (pinfunction "2_2") (pintype "passive"))
      (node (ref "U4") (pin "17") (pinfunction "RF2_17") (pintype "passive"))
    )
    (net (code "41") (name "Net-(U4-RF3)") (class "Default")
      (node (ref "C16") (pin "1") (pinfunction "1_1") (pintype "passive"))
      (node (ref "C8") (pin "2") (pinfunction "2_2") (pintype "passive"))
      (node (ref "L49") (pin "1") (pinfunction "1_1") (pintype "passive"))
      (node (ref "U4") (pin "7") (pinfunction "RF3_7") (pintype "passive"))
    )
    (net (code "42") (name "Net-(U4-RF4)") (class "Default")
      (node (ref "C13") (pin "2") (pinfunction "2_2") (pintype "passive"))
      (node (ref "L4") (pin "2") (pinfunction "2_2") (pintype "passive"))
      (node (ref "L7") (pin "1") (pinfunction "1_1") (pintype "passive"))
      (node (ref "U4") (pin "14") (pinfunction "RF4_14") (pintype "passive"))
    )
    (net (code "43") (name "Net-(U13-RF1)") (class "Default")
      (node (ref "U13") (pin "8") (pinfunction "RF1_8") (pintype "passive"))
      (node (ref "U16") (pin "10") (pinfunction "RFC_10") (pintype "passive"))
      (node (ref "U4") (pin "10") (pinfunction "RFC_10") (pintype "passive"))
    )
    (net (code "44") (name "Net-(U13-RF2)") (class "Default")
      (node (ref "U13") (pin "5") (pinfunction "RF2_5") (pintype "passive"))
      (node (ref "U14") (pin "5") (pinfunction "RF2_5") (pintype "passive"))
    )
    (net (code "45") (name "Net-(U14-RF1)") (class "Default")
      (node (ref "U14") (pin "8") (pinfunction "RF1_8") (pintype "passive"))
      (node (ref "U15") (pin "10") (pinfunction "RFC_10") (pintype "passive"))
      (node (ref "U17") (pin "10") (pinfunction "RFC_10") (pintype "passive"))
    )
    (net (code "46") (name "Net-(U15-RF1)") (class "Default")
      (node (ref "C6") (pin "1") (pinfunction "1_1") (pintype "passive"))
      (node (ref "L3") (pin "2") (pinfunction "2_2") (pintype "passive"))
      (node (ref "U15") (pin "4") (pinfunction "RF1_4") (pintype "passive"))
    )
    (net (code "47") (name "Net-(U15-RF2)") (class "Default")
      (node (ref "C21") (pin "1") (pinfunction "1_1") (pintype "passive"))
      (node (ref "C24") (pin "2") (pinfunction "2_2") (pintype "passive"))
      (node (ref "L11") (pin "2") (pinfunction "2_2") (pintype "passive"))
      (node (ref "U15") (pin "17") (pinfunction "RF2_17") (pintype "passive"))
    )
    (net (code "48") (name "Net-(U15-RF3)") (class "Default")
      (node (ref "C87") (pin "1") (pinfunction "1_1") (pintype "passive"))
      (node (ref "C90") (pin "2") (pinfunction "2_2") (pintype "passive"))
      (node (ref "L36") (pin "2") (pinfunction "2_2") (pintype "passive"))
      (node (ref "U15") (pin "7") (pinfunction "RF3_7") (pintype "passive"))
    )
    (net (code "49") (name "Net-(U15-RF4)") (class "Default")
      (node (ref "C12") (pin "1") (pinfunction "1_1") (pintype "passive"))
      (node (ref "C15") (pin "2") (pinfunction "2_2") (pintype "passive"))
      (node (ref "L6") (pin "2") (pinfunction "2_2") (pintype "passive"))
      (node (ref "U15") (pin "14") (pinfunction "RF4_14") (pintype "passive"))
    )
    (net (code "50") (name "Net-(U16-RF1)") (class "Default")
      (node (ref "C46") (pin "2") (pinfunction "2_2") (pintype "passive"))
      (node (ref "L19") (pin "2") (pinfunction "2_2") (pintype "passive"))
      (node (ref "L22") (pin "1") (pinfunction "1_1") (pintype "passive"))
      (node (ref "U16") (pin "4") (pinfunction "RF1_4") (pintype "passive"))
    )
    (net (code "51") (name "Net-(U16-RF2)") (class "Default")
      (node (ref "C74") (pin "2") (pinfunction "2_2") (pintype "passive"))
      (node (ref "L29") (pin "2") (pinfunction "2_2") (pintype "passive"))
      (node (ref "L32") (pin "1") (pinfunction "1_1") (pintype "passive"))
      (node (ref "U16") (pin "17") (pinfunction "RF2_17") (pintype "passive"))
    )
    (net (code "52") (name "Net-(U16-RF3)") (class "Default")
      (node (ref "C34") (pin "2") (pinfunction "2_2") (pintype "passive"))
      (node (ref "L14") (pin "2") (pinfunction "2_2") (pintype "passive"))
      (node (ref "L17") (pin "1") (pinfunction "1_1") (pintype "passive"))
      (node (ref "U16") (pin "7") (pinfunction "RF3_7") (pintype "passive"))
    )
    (net (code "53") (name "Net-(U16-RF4)") (class "Default")
      (node (ref "C60") (pin "2") (pinfunction "2_2") (pintype "passive"))
      (node (ref "L24") (pin "2") (pinfunction "2_2") (pintype "passive"))
      (node (ref "L27") (pin "1") (pinfunction "1_1") (pintype "passive"))
      (node (ref "U16") (pin "14") (pinfunction "RF4_14") (pintype "passive"))
    )
    (net (code "54") (name "Net-(U17-RF1)") (class "Default")
      (node (ref "C45") (pin "1") (pinfunction "1_1") (pintype "passive"))
      (node (ref "C48") (pin "2") (pinfunction "2_2") (pintype "passive"))
      (node (ref "L21") (pin "2") (pinfunction "2_2") (pintype "passive"))
      (node (ref "U17") (pin "4") (pinfunction "RF1_4") (pintype "passive"))
    )
    (net (code "55") (name "Net-(U17-RF2)") (class "Default")
      (node (ref "C73") (pin "1") (pinfunction "1_1") (pintype "passive"))
      (node (ref "C76") (pin "2") (pinfunction "2_2") (pintype "passive"))
      (node (ref "L31") (pin "2") (pinfunction "2_2") (pintype "passive"))
      (node (ref "U17") (pin "17") (pinfunction "RF2_17") (pintype "passive"))
    )
    (net (code "56") (name "Net-(U17-RF3)") (class "Default")
      (node (ref "C33") (pin "1") (pinfunction "1_1") (pintype "passive"))
      (node (ref "C36") (pin "2") (pinfunction "2_2") (pintype "passive"))
      (node (ref "L16") (pin "2") (pinfunction "2_2") (pintype "passive"))
      (node (ref "U17") (pin "7") (pinfunction "RF3_7") (pintype "passive"))
    )
    (net (code "57") (name "Net-(U17-RF4)") (class "Default")
      (node (ref "C59") (pin "1") (pinfunction "1_1") (pintype "passive"))
      (node (ref "C62") (pin "2") (pinfunction "2_2") (pintype "passive"))
      (node (ref "L26") (pin "2") (pinfunction "2_2") (pintype "passive"))
      (node (ref "U17") (pin "14") (pinfunction "RF4_14") (pintype "passive"))
    )
  )
)
